# TeleMonitor.net
KiCad netlist of a schematic drawn in EAGLE
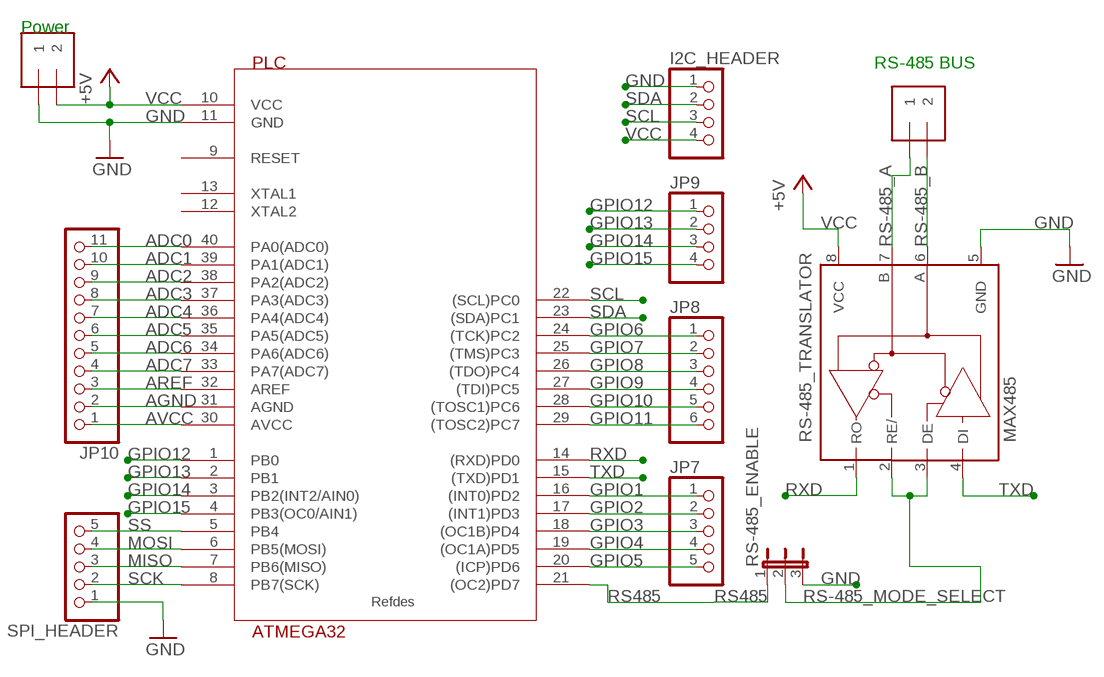
[diagram p0: schematic, sheet 1]

(export (version "E")
  (design (tool "Eeschema 10.0.6"))
  (components
    (comp (ref "I2C_HEADER")
      (value "PINHD-1X4")
      (footprint "eagle-import:1X04")
      (libsource (lib "eagle-import") (part "PINHD-1X4"))
    )
    (comp (ref "JP7")
      (value "PINHD-1X5")
      (footprint "eagle-import:1X05")
      (libsource (lib "eagle-import") (part "PINHD-1X5"))
    )
    (comp (ref "JP8")
      (value "PINHD-1X6")
      (footprint "eagle-import:1X06")
      (libsource (lib "eagle-import") (part "PINHD-1X6"))
    )
    (comp (ref "JP9")
      (value "PINHD-1X4")
      (footprint "eagle-import:1X04")
      (libsource (lib "eagle-import") (part "PINHD-1X4"))
    )
    (comp (ref "JP10")
      (value "PINHD-1X11")
      (footprint "eagle-import:1X11")
      (libsource (lib "eagle-import") (part "PINHD-1X11"))
    )
    (comp (ref "PLC")
      (value "ATMEGA32")
      (footprint "eagle-import:DIL40")
      (libsource (lib "eagle-import") (part "ATMEGA32-PU"))
    )
    (comp (ref "POWER")
      (value "5MM_TERMINAL_BLOCK-3.5MM")
      (footprint "eagle-import:1X2-3.5MM")
      (libsource (lib "eagle-import") (part "5MM_TERMINAL_BLOCK-3.5MM"))
    )
    (comp (ref "RS-485")
      (value "5MM_TERMINAL_BLOCK-3.5MM")
      (footprint "eagle-import:1X2-3.5MM")
      (libsource (lib "eagle-import") (part "5MM_TERMINAL_BLOCK-3.5MM"))
    )
    (comp (ref "RS-485_ENABLE")
      (value "JP2E")
      (footprint "eagle-import:JP2")
      (libsource (lib "eagle-import") (part "JP2E"))
    )
    (comp (ref "RS-485_TRANSLATOR")
      (value "MAX485")
      (footprint "eagle-import:DIL08")
      (libsource (lib "eagle-import") (part "MAX34PA68C"))
    )
    (comp (ref "SPI_HEADER")
      (value "PINHD-1X5")
      (footprint "eagle-import:1X05")
      (libsource (lib "eagle-import") (part "PINHD-1X5"))
    )
  )
  (nets
    (net (code "1") (name "+5V") (class "Default")
      (node (ref "I2C_HEADER") (pin "4") (pinfunction "4_4") (pintype "passive"))
      (node (ref "PLC") (pin "10") (pinfunction "VCC_10") (pintype "power_in"))
      (node (ref "POWER") (pin "2") (pinfunction "2_2") (pintype "passive"))
      (node (ref "RS-485_TRANSLATOR") (pin "8") (pinfunction "VCC_8") (pintype "power_in"))
    )
    (net (code "2") (name "/ADC0") (class "Default")
      (node (ref "JP10") (pin "11") (pinfunction "11_11") (pintype "passive"))
      (node (ref "PLC") (pin "40") (pinfunction "PA0(ADC0)_40") (pintype "bidirectional"))
    )
    (net (code "3") (name "/ADC1") (class "Default")
      (node (ref "JP10") (pin "10") (pinfunction "10_10") (pintype "passive"))
      (node (ref "PLC") (pin "39") (pinfunction "PA1(ADC1)_39") (pintype "bidirectional"))
    )
    (net (code "4") (name "/ADC2") (class "Default")
      (node (ref "JP10") (pin "9") (pinfunction "9_9") (pintype "passive"))
      (node (ref "PLC") (pin "38") (pinfunction "PA2(ADC2)_38") (pintype "bidirectional"))
    )
    (net (code "5") (name "/ADC3") (class "Default")
      (node (ref "JP10") (pin "8") (pinfunction "8_8") (pintype "passive"))
      (node (ref "PLC") (pin "37") (pinfunction "PA3(ADC3)_37") (pintype "bidirectional"))
    )
    (net (code "6") (name "/ADC4") (class "Default")
      (node (ref "JP10") (pin "7") (pinfunction "7_7") (pintype "passive"))
      (node (ref "PLC") (pin "36") (pinfunction "PA4(ADC4)_36") (pintype "bidirectional"))
    )
    (net (code "7") (name "/ADC5") (class "Default")
      (node (ref "JP10") (pin "6") (pinfunction "6_6") (pintype "passive"))
      (node (ref "PLC") (pin "35") (pinfunction "PA5(ADC5)_35") (pintype "bidirectional"))
    )
    (net (code "8") (name "/ADC6") (class "Default")
      (node (ref "JP10") (pin "5") (pinfunction "5_5") (pintype "passive"))
      (node (ref "PLC") (pin "34") (pinfunction "PA6(ADC6)_34") (pintype "bidirectional"))
    )
    (net (code "9") (name "/ADC7") (class "Default")
      (node (ref "JP10") (pin "4") (pinfunction "4_4") (pintype "passive"))
      (node (ref "PLC") (pin "33") (pinfunction "PA7(ADC7)_33") (pintype "bidirectional"))
    )
    (net (code "10") (name "/AGND") (class "Default")
      (node (ref "JP10") (pin "2") (pinfunction "2_2") (pintype "passive"))
      (node (ref "PLC") (pin "31") (pinfunction "AGND_31") (pintype "passive"))
    )
    (net (code "11") (name "/AREF") (class "Default")
      (node (ref "JP10") (pin "3") (pinfunction "3_3") (pintype "passive"))
      (node (ref "PLC") (pin "32") (pinfunction "AREF_32") (pintype "input"))
    )
    (net (code "12") (name "/AVCC") (class "Default")
      (node (ref "JP10") (pin "1") (pinfunction "1_1") (pintype "passive"))
      (node (ref "PLC") (pin "30") (pinfunction "AVCC_30") (pintype "power_in"))
    )
    (net (code "13") (name "/GPIO1") (class "Default")
      (node (ref "JP7") (pin "1") (pinfunction "1_1") (pintype "passive"))
      (node (ref "PLC") (pin "16") (pinfunction "(INT0)PD2_16") (pintype "bidirectional"))
    )
    (net (code "14") (name "/GPIO2") (class "Default")
      (node (ref "JP7") (pin "2") (pinfunction "2_2") (pintype "passive"))
      (node (ref "PLC") (pin "17") (pinfunction "(INT1)PD3_17") (pintype "bidirectional"))
    )
    (net (code "15") (name "/GPIO3") (class "Default")
      (node (ref "JP7") (pin "3") (pinfunction "3_3") (pintype "passive"))
      (node (ref "PLC") (pin "18") (pinfunction "(OC1B)PD4_18") (pintype "bidirectional"))
    )
    (net (code "16") (name "/GPIO4") (class "Default")
      (node (ref "JP7") (pin "4") (pinfunction "4_4") (pintype "passive"))
      (node (ref "PLC") (pin "19") (pinfunction "(OC1A)PD5_19") (pintype "bidirectional"))
    )
    (net (code "17") (name "/GPIO5") (class "Default")
      (node (ref "JP7") (pin "5") (pinfunction "5_5") (pintype "passive"))
      (node (ref "PLC") (pin "20") (pinfunction "(ICP)PD6_20") (pintype "bidirectional"))
    )
    (net (code "18") (name "/GPIO6") (class "Default")
      (node (ref "JP8") (pin "1") (pinfunction "1_1") (pintype "passive"))
      (node (ref "PLC") (pin "24") (pinfunction "(TCK)PC2_24") (pintype "bidirectional"))
    )
    (net (code "19") (name "/GPIO7") (class "Default")
      (node (ref "JP8") (pin "2") (pinfunction "2_2") (pintype "passive"))
      (node (ref "PLC") (pin "25") (pinfunction "(TMS)PC3_25") (pintype "bidirectional"))
    )
    (net (code "20") (name "/GPIO8") (class "Default")
      (node (ref "JP8") (pin "3") (pinfunction "3_3") (pintype "passive"))
      (node (ref "PLC") (pin "26") (pinfunction "(TDO)PC4_26") (pintype "bidirectional"))
    )
    (net (code "21") (name "/GPIO9") (class "Default")
      (node (ref "JP8") (pin "4") (pinfunction "4_4") (pintype "passive"))
      (node (ref "PLC") (pin "27") (pinfunction "(TDI)PC5_27") (pintype "bidirectional"))
    )
    (net (code "22") (name "/GPIO10") (class "Default")
      (node (ref "JP8") (pin "5") (pinfunction "5_5") (pintype "passive"))
      (node (ref "PLC") (pin "28") (pinfunction "(TOSC1)PC6_28") (pintype "bidirectional"))
    )
    (net (code "23") (name "/GPIO11") (class "Default")
      (node (ref "JP8") (pin "6") (pinfunction "6_6") (pintype "passive"))
      (node (ref "PLC") (pin "29") (pinfunction "(TOSC2)PC7_29") (pintype "bidirectional"))
    )
    (net (code "24") (name "/GPIO12") (class "Default")
      (node (ref "JP9") (pin "1") (pinfunction "1_1") (pintype "passive"))
      (node (ref "PLC") (pin "1") (pinfunction "PB0_1") (pintype "bidirectional"))
    )
    (net (code "25") (name "/GPIO13") (class "Default")
      (node (ref "JP9") (pin "2") (pinfunction "2_2") (pintype "passive"))
      (node (ref "PLC") (pin "2") (pinfunction "PB1_2") (pintype "bidirectional"))
    )
    (net (code "26") (name "/GPIO14") (class "Default")
      (node (ref "JP9") (pin "3") (pinfunction "3_3") (pintype "passive"))
      (node (ref "PLC") (pin "3") (pinfunction "PB2(INT2/AIN0)_3") (pintype "bidirectional"))
    )
    (net (code "27") (name "/GPIO15") (class "Default")
      (node (ref "JP9") (pin "4") (pinfunction "4_4") (pintype "passive"))
      (node (ref "PLC") (pin "4") (pinfunction "PB3(OC0/AIN1)_4") (pintype "bidirectional"))
    )
    (net (code "28") (name "/MISO") (class "Default")
      (node (ref "PLC") (pin "7") (pinfunction "PB6(MISO)_7") (pintype "bidirectional"))
      (node (ref "SPI_HEADER") (pin "3") (pinfunction "3_3") (pintype "passive"))
    )
    (net (code "29") (name "/MOSI") (class "Default")
      (node (ref "PLC") (pin "6") (pinfunction "PB5(MOSI)_6") (pintype "bidirectional"))
      (node (ref "SPI_HEADER") (pin "4") (pinfunction "4_4") (pintype "passive"))
    )
    (net (code "30") (name "/RS-485_A") (class "Default")
      (node (ref "RS-485") (pin "1") (pinfunction "1_1") (pintype "passive"))
      (node (ref "RS-485_TRANSLATOR") (pin "7") (pinfunction "B_7") (pintype "passive"))
    )
    (net (code "31") (name "/RS-485_B") (class "Default")
      (node (ref "RS-485") (pin "2") (pinfunction "2_2") (pintype "passive"))
      (node (ref "RS-485_TRANSLATOR") (pin "6") (pinfunction "A_6") (pintype "passive"))
    )
    (net (code "32") (name "/RS-485_MODE_SELECT") (class "Default")
      (node (ref "RS-485_ENABLE") (pin "2") (pinfunction "2_2") (pintype "passive"))
      (node (ref "RS-485_TRANSLATOR") (pin "2") (pinfunction "RE/_2") (pintype "input"))
      (node (ref "RS-485_TRANSLATOR") (pin "3") (pinfunction "DE_3") (pintype "input"))
    )
    (net (code "33") (name "/RS485") (class "Default")
      (node (ref "PLC") (pin "21") (pinfunction "(OC2)PD7_21") (pintype "bidirectional"))
      (node (ref "RS-485_ENABLE") (pin "1") (pinfunction "1_1") (pintype "passive"))
    )
    (net (code "34") (name "/RXD") (class "Default")
      (node (ref "PLC") (pin "14") (pinfunction "(RXD)PD0_14") (pintype "bidirectional"))
      (node (ref "RS-485_TRANSLATOR") (pin "1") (pinfunction "RO_1") (pintype "output"))
    )
    (net (code "35") (name "/SCK") (class "Default")
      (node (ref "PLC") (pin "8") (pinfunction "PB7(SCK)_8") (pintype "bidirectional"))
      (node (ref "SPI_HEADER") (pin "2") (pinfunction "2_2") (pintype "passive"))
    )
    (net (code "36") (name "/SCL") (class "Default")
      (node (ref "I2C_HEADER") (pin "3") (pinfunction "3_3") (pintype "passive"))
      (node (ref "PLC") (pin "22") (pinfunction "(SCL)PC0_22") (pintype "bidirectional"))
    )
    (net (code "37") (name "/SDA") (class "Default")
      (node (ref "I2C_HEADER") (pin "2") (pinfunction "2_2") (pintype "passive"))
      (node (ref "PLC") (pin "23") (pinfunction "(SDA)PC1_23") (pintype "bidirectional"))
    )
    (net (code "38") (name "/SS") (class "Default")
      (node (ref "PLC") (pin "5") (pinfunction "PB4_5") (pintype "bidirectional"))
      (node (ref "SPI_HEADER") (pin "5") (pinfunction "5_5") (pintype "passive"))
    )
    (net (code "39") (name "/TXD") (class "Default")
      (node (ref "PLC") (pin "15") (pinfunction "(TXD)PD1_15") (pintype "bidirectional"))
      (node (ref "RS-485_TRANSLATOR") (pin "4") (pinfunction "DI_4") (pintype "input"))
    )
    (net (code "40") (name "GND") (class "Default")
      (node (ref "I2C_HEADER") (pin "1") (pinfunction "1_1") (pintype "passive"))
      (node (ref "PLC") (pin "11") (pinfunction "GND_11") (pintype "passive"))
      (node (ref "POWER") (pin "1") (pinfunction "1_1") (pintype "passive"))
      (node (ref "RS-485_ENABLE") (pin "3") (pinfunction "3_3") (pintype "passive"))
      (node (ref "RS-485_TRANSLATOR") (pin "5") (pinfunction "GND_5") (pintype "power_in"))
      (node (ref "SPI_HEADER") (pin "1") (pinfunction "1_1") (pintype "passive"))
    )
    (net (code "41") (name "unconnected-(PLC-RESET-Pad9)") (class "Default")
      (node (ref "PLC") (pin "9") (pinfunction "RESET_9") (pintype "input"))
    )
    (net (code "42") (name "unconnected-(PLC-XTAL1-Pad13)") (class "Default")
      (node (ref "PLC") (pin "13") (pinfunction "XTAL1_13") (pintype "input"))
    )
    (net (code "43") (name "unconnected-(PLC-XTAL2-Pad12)") (class "Default")
      (node (ref "PLC") (pin "12") (pinfunction "XTAL2_12") (pintype "output"))
    )
  )
)
